# Driver.net
KiCad netlist of a schematic drawn in Altium Designer
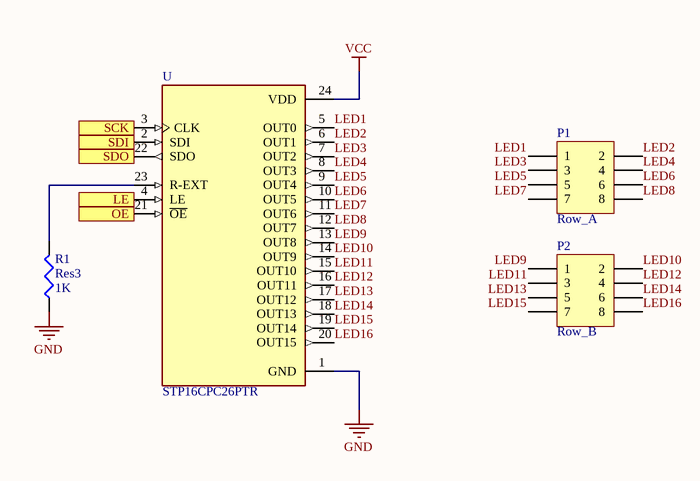
[diagram p0: Driver.SchDoc]

(export (version "E")
  (design (tool "Eeschema 10.0.6"))
  (components
    (comp (ref "P1")
      (value "Row_A")
      (footprint "HDR2X4H")
      (description "Header, 4-Pin, Dual row, Right Angle")
      (fields (field (name "PUBLISHER") "Altium Limited"))
      (libsource (lib "Miscellaneous Connectors") (part "Header 4X2H"))
    )
    (comp (ref "P2")
      (value "Row_B")
      (footprint "HDR2X4H")
      (description "Header, 4-Pin, Dual row, Right Angle")
      (fields (field (name "PUBLISHER") "Altium Limited"))
      (libsource (lib "Miscellaneous Connectors") (part "Header 4X2H"))
    )
    (comp (ref "R1")
      (value "Res3")
      (footprint "1608[0603]")
      (description "Resistor")
      (fields (field (name "ALTIUM_VALUE") "1K") (field (name "PUBLISHER") "Altium Limited"))
      (libsource (lib "Miscellaneous Devices") (part "Res3"))
    )
    (comp (ref "U")
      (value "STP16CPC26PTR")
      (footprint "TSOP65P700X110_HS-25N")
      (description "LED Driver IC 16 Output Linear Shift Register Analog Dimming 90mA 24-QSOP")
      (fields (field (name "MF") "STMicroelectronics"))
      (libsource (lib "STP16CPC26PTR") (part "STP16CPC26PTR"))
    )
  )
  (nets
    (net (code "1") (name "/LE") (class "Default")
      (node (ref "U") (pin "4") (pinfunction "LE_4") (pintype "input"))
    )
    (net (code "2") (name "/LED1") (class "Default")
      (node (ref "P1") (pin "1") (pinfunction "1_1") (pintype "passive"))
      (node (ref "U") (pin "5") (pinfunction "OUT0_5") (pintype "output"))
    )
    (net (code "3") (name "/LED2") (class "Default")
      (node (ref "P1") (pin "2") (pinfunction "2_2") (pintype "passive"))
      (node (ref "U") (pin "6") (pinfunction "OUT1_6") (pintype "output"))
    )
    (net (code "4") (name "/LED3") (class "Default")
      (node (ref "P1") (pin "3") (pinfunction "3_3") (pintype "passive"))
      (node (ref "U") (pin "7") (pinfunction "OUT2_7") (pintype "output"))
    )
    (net (code "5") (name "/LED4") (class "Default")
      (node (ref "P1") (pin "4") (pinfunction "4_4") (pintype "passive"))
      (node (ref "U") (pin "8") (pinfunction "OUT3_8") (pintype "output"))
    )
    (net (code "6") (name "/LED5") (class "Default")
      (node (ref "P1") (pin "5") (pinfunction "5_5") (pintype "passive"))
      (node (ref "U") (pin "9") (pinfunction "OUT4_9") (pintype "output"))
    )
    (net (code "7") (name "/LED6") (class "Default")
      (node (ref "P1") (pin "6") (pinfunction "6_6") (pintype "passive"))
      (node (ref "U") (pin "10") (pinfunction "OUT5_10") (pintype "output"))
    )
    (net (code "8") (name "/LED7") (class "Default")
      (node (ref "P1") (pin "7") (pinfunction "7_7") (pintype "passive"))
      (node (ref "U") (pin "11") (pinfunction "OUT6_11") (pintype "output"))
    )
    (net (code "9") (name "/LED8") (class "Default")
      (node (ref "P1") (pin "8") (pinfunction "8_8") (pintype "passive"))
      (node (ref "U") (pin "12") (pinfunction "OUT7_12") (pintype "output"))
    )
    (net (code "10") (name "/LED9") (class "Default")
      (node (ref "P2") (pin "1") (pinfunction "1_1") (pintype "passive"))
      (node (ref "U") (pin "13") (pinfunction "OUT8_13") (pintype "output"))
    )
    (net (code "11") (name "/LED10") (class "Default")
      (node (ref "P2") (pin "2") (pinfunction "2_2") (pintype "passive"))
      (node (ref "U") (pin "14") (pinfunction "OUT9_14") (pintype "output"))
    )
    (net (code "12") (name "/LED11") (class "Default")
      (node (ref "P2") (pin "3") (pinfunction "3_3") (pintype "passive"))
      (node (ref "U") (pin "15") (pinfunction "OUT10_15") (pintype "output"))
    )
    (net (code "13") (name "/LED12") (class "Default")
      (node (ref "P2") (pin "4") (pinfunction "4_4") (pintype "passive"))
      (node (ref "U") (pin "16") (pinfunction "OUT11_16") (pintype "output"))
    )
    (net (code "14") (name "/LED13") (class "Default")
      (node (ref "P2") (pin "5") (pinfunction "5_5") (pintype "passive"))
      (node (ref "U") (pin "17") (pinfunction "OUT12_17") (pintype "output"))
    )
    (net (code "15") (name "/LED14") (class "Default")
      (node (ref "P2") (pin "6") (pinfunction "6_6") (pintype "passive"))
      (node (ref "U") (pin "18") (pinfunction "OUT13_18") (pintype "output"))
    )
    (net (code "16") (name "/LED15") (class "Default")
      (node (ref "P2") (pin "7") (pinfunction "7_7") (pintype "passive"))
      (node (ref "U") (pin "19") (pinfunction "OUT14_19") (pintype "output"))
    )
    (net (code "17") (name "/LED16") (class "Default")
      (node (ref "P2") (pin "8") (pinfunction "8_8") (pintype "passive"))
      (node (ref "U") (pin "20") (pinfunction "OUT15_20") (pintype "output"))
    )
    (net (code "18") (name "/OE") (class "Default")
      (node (ref "U") (pin "21") (pinfunction "~{OE}_21") (pintype "input"))
    )
    (net (code "19") (name "/SCK") (class "Default")
      (node (ref "U") (pin "3") (pinfunction "CLK_3") (pintype "input"))
    )
    (net (code "20") (name "/SDI") (class "Default")
      (node (ref "U") (pin "2") (pinfunction "SDI_2") (pintype "input"))
    )
    (net (code "21") (name "/SDO") (class "Default")
      (node (ref "U") (pin "22") (pinfunction "SDO_22") (pintype "output"))
    )
    (net (code "22") (name "GND") (class "Default")
      (node (ref "R1") (pin "1") (pinfunction "1_1") (pintype "passive"))
      (node (ref "U") (pin "1") (pinfunction "GND_1") (pintype "power_in"))
    )
    (net (code "23") (name "Net-(U-R-EXT)") (class "Default")
      (node (ref "R1") (pin "2") (pinfunction "2_2") (pintype "passive"))
      (node (ref "U") (pin "23") (pinfunction "R-EXT_23") (pintype "input"))
    )
    (net (code "24") (name "VCC") (class "Default")
      (node (ref "U") (pin "24") (pinfunction "VDD_24") (pintype "power_in"))
    )
  )
)
